# HEADER_WRP.net
KiCad netlist of a schematic drawn in Altium Designer
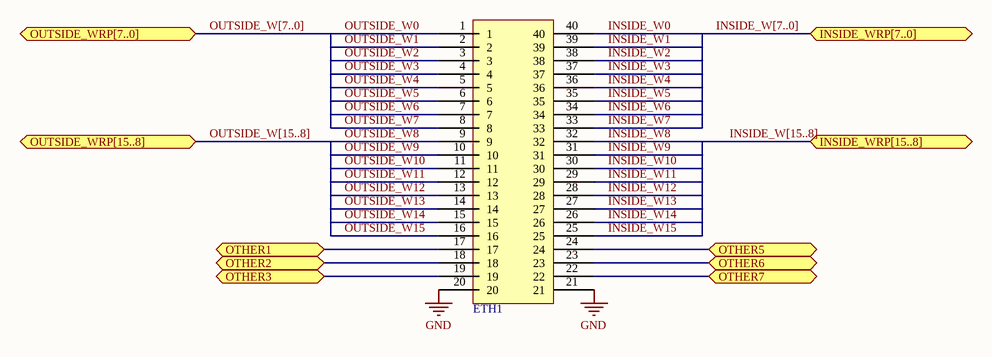
[diagram p0: HEADER_WRP.SchDoc]

(export (version "E")
  (design (tool "Eeschema 10.0.6"))
  (components
    (comp (ref "ETH1")
      (value "ADAFRUIT_HEADER")
      (footprint "FEMALE_HEADER_SMD")
      (description "Extra tall female header (SMD)")
      (libsource (lib "DUTBoard") (part "ADAFRUIT_HEADER"))
    )
  )
  (nets
    (net (code "1") (name "/INSIDE_W0") (class "Default")
      (node (ref "ETH1") (pin "40") (pinfunction "40_40") (pintype "passive"))
    )
    (net (code "2") (name "/INSIDE_W1") (class "Default")
      (node (ref "ETH1") (pin "39") (pinfunction "39_39") (pintype "passive"))
    )
    (net (code "3") (name "/INSIDE_W2") (class "Default")
      (node (ref "ETH1") (pin "38") (pinfunction "38_38") (pintype "passive"))
    )
    (net (code "4") (name "/INSIDE_W3") (class "Default")
      (node (ref "ETH1") (pin "37") (pinfunction "37_37") (pintype "passive"))
    )
    (net (code "5") (name "/INSIDE_W4") (class "Default")
      (node (ref "ETH1") (pin "36") (pinfunction "36_36") (pintype "passive"))
    )
    (net (code "6") (name "/INSIDE_W5") (class "Default")
      (node (ref "ETH1") (pin "35") (pinfunction "35_35") (pintype "passive"))
    )
    (net (code "7") (name "/INSIDE_W6") (class "Default")
      (node (ref "ETH1") (pin "34") (pinfunction "34_34") (pintype "passive"))
    )
    (net (code "8") (name "/INSIDE_W7") (class "Default")
      (node (ref "ETH1") (pin "33") (pinfunction "33_33") (pintype "passive"))
    )
    (net (code "9") (name "/INSIDE_W8") (class "Default")
      (node (ref "ETH1") (pin "32") (pinfunction "32_32") (pintype "passive"))
    )
    (net (code "10") (name "/INSIDE_W9") (class "Default")
      (node (ref "ETH1") (pin "31") (pinfunction "31_31") (pintype "passive"))
    )
    (net (code "11") (name "/INSIDE_W10") (class "Default")
      (node (ref "ETH1") (pin "30") (pinfunction "30_30") (pintype "passive"))
    )
    (net (code "12") (name "/INSIDE_W11") (class "Default")
      (node (ref "ETH1") (pin "29") (pinfunction "29_29") (pintype "passive"))
    )
    (net (code "13") (name "/INSIDE_W12") (class "Default")
      (node (ref "ETH1") (pin "28") (pinfunction "28_28") (pintype "passive"))
    )
    (net (code "14") (name "/INSIDE_W13") (class "Default")
      (node (ref "ETH1") (pin "27") (pinfunction "27_27") (pintype "passive"))
    )
    (net (code "15") (name "/INSIDE_W14") (class "Default")
      (node (ref "ETH1") (pin "26") (pinfunction "26_26") (pintype "passive"))
    )
    (net (code "16") (name "/INSIDE_W15") (class "Default")
      (node (ref "ETH1") (pin "25") (pinfunction "25_25") (pintype "passive"))
    )
    (net (code "19") (name "/OTHER1") (class "Default")
      (node (ref "ETH1") (pin "17") (pinfunction "17_17") (pintype "passive"))
    )
    (net (code "20") (name "/OTHER2") (class "Default")
      (node (ref "ETH1") (pin "18") (pinfunction "18_18") (pintype "passive"))
    )
    (net (code "21") (name "/OTHER3") (class "Default")
      (node (ref "ETH1") (pin "19") (pinfunction "19_19") (pintype "passive"))
    )
    (net (code "22") (name "/OTHER5") (class "Default")
      (node (ref "ETH1") (pin "24") (pinfunction "24_24") (pintype "passive"))
    )
    (net (code "23") (name "/OTHER6") (class "Default")
      (node (ref "ETH1") (pin "23") (pinfunction "23_23") (pintype "passive"))
    )
    (net (code "24") (name "/OTHER7") (class "Default")
      (node (ref "ETH1") (pin "22") (pinfunction "22_22") (pintype "passive"))
    )
    (net (code "25") (name "/OUTSIDE_W0") (class "Default")
      (node (ref "ETH1") (pin "1") (pinfunction "1_1") (pintype "passive"))
    )
    (net (code "26") (name "/OUTSIDE_W1") (class "Default")
      (node (ref "ETH1") (pin "2") (pinfunction "2_2") (pintype "passive"))
    )
    (net (code "27") (name "/OUTSIDE_W2") (class "Default")
      (node (ref "ETH1") (pin "3") (pinfunction "3_3") (pintype "passive"))
    )
    (net (code "28") (name "/OUTSIDE_W3") (class "Default")
      (node (ref "ETH1") (pin "4") (pinfunction "4_4") (pintype "passive"))
    )
    (net (code "29") (name "/OUTSIDE_W4") (class "Default")
      (node (ref "ETH1") (pin "5") (pinfunction "5_5") (pintype "passive"))
    )
    (net (code "30") (name "/OUTSIDE_W5") (class "Default")
      (node (ref "ETH1") (pin "6") (pinfunction "6_6") (pintype "passive"))
    )
    (net (code "31") (name "/OUTSIDE_W6") (class "Default")
      (node (ref "ETH1") (pin "7") (pinfunction "7_7") (pintype "passive"))
    )
    (net (code "32") (name "/OUTSIDE_W7") (class "Default")
      (node (ref "ETH1") (pin "8") (pinfunction "8_8") (pintype "passive"))
    )
    (net (code "33") (name "/OUTSIDE_W8") (class "Default")
      (node (ref "ETH1") (pin "9") (pinfunction "9_9") (pintype "passive"))
    )
    (net (code "34") (name "/OUTSIDE_W9") (class "Default")
      (node (ref "ETH1") (pin "10") (pinfunction "10_10") (pintype "passive"))
    )
    (net (code "35") (name "/OUTSIDE_W10") (class "Default")
      (node (ref "ETH1") (pin "11") (pinfunction "11_11") (pintype "passive"))
    )
    (net (code "36") (name "/OUTSIDE_W11") (class "Default")
      (node (ref "ETH1") (pin "12") (pinfunction "12_12") (pintype "passive"))
    )
    (net (code "37") (name "/OUTSIDE_W12") (class "Default")
      (node (ref "ETH1") (pin "13") (pinfunction "13_13") (pintype "passive"))
    )
    (net (code "38") (name "/OUTSIDE_W13") (class "Default")
      (node (ref "ETH1") (pin "14") (pinfunction "14_14") (pintype "passive"))
    )
    (net (code "39") (name "/OUTSIDE_W14") (class "Default")
      (node (ref "ETH1") (pin "15") (pinfunction "15_15") (pintype "passive"))
    )
    (net (code "40") (name "/OUTSIDE_W15") (class "Default")
      (node (ref "ETH1") (pin "16") (pinfunction "16_16") (pintype "passive"))
    )
    (net (code "43") (name "GND") (class "Default")
      (node (ref "ETH1") (pin "20") (pinfunction "20_20") (pintype "passive"))
      (node (ref "ETH1") (pin "21") (pinfunction "21_21") (pintype "passive"))
    )
  )
)
